# DVforArduino.net
KiCad netlist of a schematic drawn in EAGLE
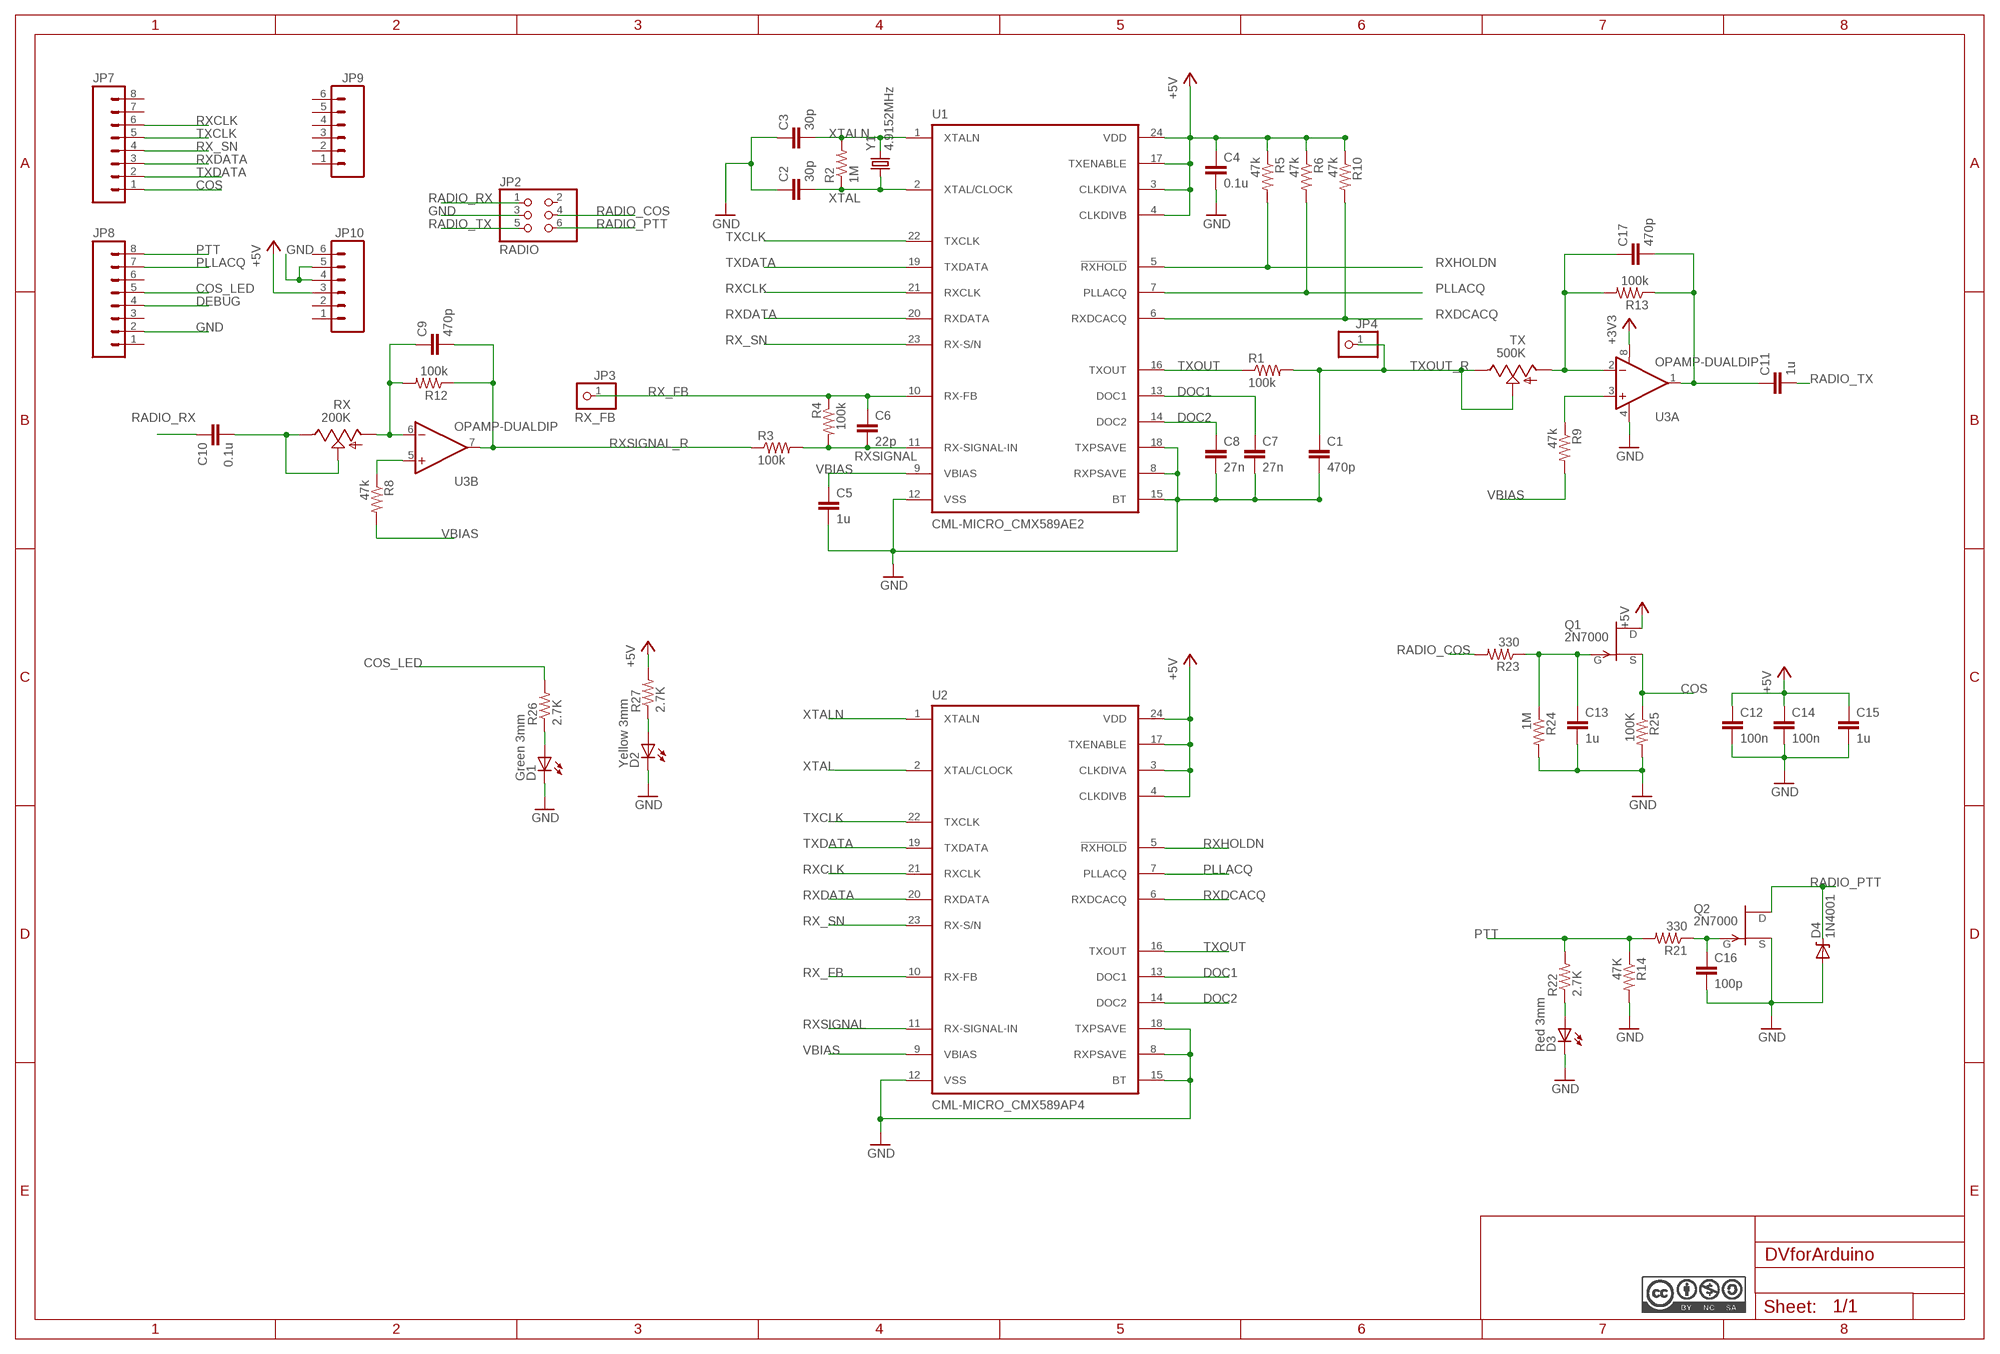
[diagram p0: schematic, sheet 1]

(export (version "E")
  (design (tool "Eeschema 10.0.6"))
  (components
    (comp (ref "C1")
      (value "470p")
      (footprint "eagle-import:C2.5-3")
      (libsource (lib "eagle-import") (part "C2,5-3"))
    )
    (comp (ref "C2")
      (value "30p")
      (footprint "eagle-import:C2.5-3")
      (libsource (lib "eagle-import") (part "C2,5-3"))
    )
    (comp (ref "C3")
      (value "30p")
      (footprint "eagle-import:C2.5-3")
      (libsource (lib "eagle-import") (part "C2,5-3"))
    )
    (comp (ref "C4")
      (value "0.1u")
      (footprint "eagle-import:C2.5-3")
      (libsource (lib "eagle-import") (part "C2,5-3"))
    )
    (comp (ref "C5")
      (value "1u")
      (footprint "eagle-import:C2.5-3")
      (libsource (lib "eagle-import") (part "C2,5-3"))
    )
    (comp (ref "C6")
      (value "22p")
      (footprint "eagle-import:C2.5-3")
      (libsource (lib "eagle-import") (part "C2,5-3"))
    )
    (comp (ref "C7")
      (value "27n")
      (footprint "eagle-import:C2.5-3")
      (libsource (lib "eagle-import") (part "C2,5-3"))
    )
    (comp (ref "C8")
      (value "27n")
      (footprint "eagle-import:C2.5-3")
      (libsource (lib "eagle-import") (part "C2,5-3"))
    )
    (comp (ref "C9")
      (value "470p")
      (footprint "eagle-import:C2.5-3")
      (libsource (lib "eagle-import") (part "C2,5-3"))
    )
    (comp (ref "C10")
      (value "0.1u")
      (footprint "eagle-import:C2.5-3")
      (libsource (lib "eagle-import") (part "C2,5-3"))
    )
    (comp (ref "C11")
      (value "1u")
      (footprint "eagle-import:C2.5-3")
      (libsource (lib "eagle-import") (part "C2,5-3"))
    )
    (comp (ref "C12")
      (value "100n")
      (footprint "eagle-import:C2.5-3")
      (libsource (lib "eagle-import") (part "C2,5-3"))
    )
    (comp (ref "C13")
      (value "1u")
      (footprint "eagle-import:C2.5-3")
      (libsource (lib "eagle-import") (part "C2,5-3"))
    )
    (comp (ref "C14")
      (value "100n")
      (footprint "eagle-import:C2.5-3")
      (libsource (lib "eagle-import") (part "C2,5-3"))
    )
    (comp (ref "C15")
      (value "1u")
      (footprint "eagle-import:C2.5-3")
      (libsource (lib "eagle-import") (part "C2,5-3"))
    )
    (comp (ref "C16")
      (value "100p")
      (footprint "eagle-import:C2.5-3")
      (libsource (lib "eagle-import") (part "C2,5-3"))
    )
    (comp (ref "C17")
      (value "470p")
      (footprint "eagle-import:C2.5-3")
      (libsource (lib "eagle-import") (part "C2,5-3"))
    )
    (comp (ref "D1")
      (value "Green 3mm")
      (footprint "eagle-import:LED3MM")
      (libsource (lib "eagle-import") (part "LED3MM"))
    )
    (comp (ref "D2")
      (value "Yellow 3mm")
      (footprint "eagle-import:LED3MM")
      (libsource (lib "eagle-import") (part "LED3MM"))
    )
    (comp (ref "D3")
      (value "Red 3mm")
      (footprint "eagle-import:LED3MM")
      (libsource (lib "eagle-import") (part "LED3MM"))
    )
    (comp (ref "D4")
      (value "1N4001")
      (footprint "eagle-import:DIODE-ZENER")
      (libsource (lib "eagle-import") (part "DIODE-ZENERPTH"))
    )
    (comp (ref "JP2")
      (value "RADIO")
      (footprint "eagle-import:2X03_ROUND_70MIL")
      (libsource (lib "eagle-import") (part "HEADER-2X3"))
    )
    (comp (ref "JP3")
      (value "RX_FB")
      (footprint "eagle-import:1X01_ROUND")
      (libsource (lib "eagle-import") (part "HEADER-1X1ROUND"))
    )
    (comp (ref "JP4")
      (value "HEADER-1X1ROUND")
      (footprint "eagle-import:1X01_ROUND")
      (libsource (lib "eagle-import") (part "HEADER-1X1ROUND"))
    )
    (comp (ref "JP7")
      (value "M081X08")
      (footprint "eagle-import:1X08")
      (libsource (lib "eagle-import") (part "M081X08"))
    )
    (comp (ref "JP8")
      (value "M081X08")
      (footprint "eagle-import:1X08")
      (libsource (lib "eagle-import") (part "M081X08"))
    )
    (comp (ref "JP9")
      (value "M06SIP")
      (footprint "eagle-import:1X06")
      (libsource (lib "eagle-import") (part "M06SIP"))
    )
    (comp (ref "JP10")
      (value "M06SIP")
      (footprint "eagle-import:1X06")
      (libsource (lib "eagle-import") (part "M06SIP"))
    )
    (comp (ref "Q1")
      (value "2N7000")
      (footprint "eagle-import:TO92")
      (libsource (lib "eagle-import") (part "2N3819"))
    )
    (comp (ref "Q2")
      (value "2N7000")
      (footprint "eagle-import:TO92")
      (libsource (lib "eagle-import") (part "2N3819"))
    )
    (comp (ref "R1")
      (value "100k")
      (footprint "eagle-import:0204V")
      (libsource (lib "eagle-import") (part "R-US_0204/2V"))
    )
    (comp (ref "R2")
      (value "1M")
      (footprint "eagle-import:0204V")
      (libsource (lib "eagle-import") (part "R-US_0204/2V"))
    )
    (comp (ref "R3")
      (value "100k")
      (footprint "eagle-import:0204V")
      (libsource (lib "eagle-import") (part "R-US_0204/2V"))
    )
    (comp (ref "R4")
      (value "100k")
      (footprint "eagle-import:0204V")
      (libsource (lib "eagle-import") (part "R-US_0204/2V"))
    )
    (comp (ref "R5")
      (value "47k")
      (footprint "eagle-import:0204V")
      (libsource (lib "eagle-import") (part "R-US_0204/2V"))
    )
    (comp (ref "R6")
      (value "47k")
      (footprint "eagle-import:0204V")
      (libsource (lib "eagle-import") (part "R-US_0204/2V"))
    )
    (comp (ref "R8")
      (value "47k")
      (footprint "eagle-import:0204V")
      (libsource (lib "eagle-import") (part "R-US_0204/2V"))
    )
    (comp (ref "R9")
      (value "47k")
      (footprint "eagle-import:0204V")
      (libsource (lib "eagle-import") (part "R-US_0204/2V"))
    )
    (comp (ref "R10")
      (value "47k")
      (footprint "eagle-import:0204V")
      (libsource (lib "eagle-import") (part "R-US_0204/2V"))
    )
    (comp (ref "R12")
      (value "100k")
      (footprint "eagle-import:0204V")
      (libsource (lib "eagle-import") (part "R-US_0204/2V"))
    )
    (comp (ref "R13")
      (value "100k")
      (footprint "eagle-import:0204V")
      (libsource (lib "eagle-import") (part "R-US_0204/2V"))
    )
    (comp (ref "R14")
      (value "47K")
      (footprint "eagle-import:0204V")
      (libsource (lib "eagle-import") (part "R-US_0204/2V"))
    )
    (comp (ref "R21")
      (value "330")
      (footprint "eagle-import:0204V")
      (libsource (lib "eagle-import") (part "R-US_0204/2V"))
    )
    (comp (ref "R22")
      (value "2.7K")
      (footprint "eagle-import:0204V")
      (libsource (lib "eagle-import") (part "R-US_0204/2V"))
    )
    (comp (ref "R23")
      (value "330")
      (footprint "eagle-import:0204V")
      (libsource (lib "eagle-import") (part "R-US_0204/2V"))
    )
    (comp (ref "R24")
      (value "1M")
      (footprint "eagle-import:0204V")
      (libsource (lib "eagle-import") (part "R-US_0204/2V"))
    )
    (comp (ref "R25")
      (value "100K")
      (footprint "eagle-import:0204V")
      (libsource (lib "eagle-import") (part "R-US_0204/2V"))
    )
    (comp (ref "R26")
      (value "2.7K")
      (footprint "eagle-import:0204V")
      (libsource (lib "eagle-import") (part "R-US_0204/2V"))
    )
    (comp (ref "R27")
      (value "2.7K")
      (footprint "eagle-import:0204V")
      (libsource (lib "eagle-import") (part "R-US_0204/2V"))
    )
    (comp (ref "RX")
      (value "200K")
      (footprint "eagle-import:B25P")
      (libsource (lib "eagle-import") (part "TRIM_US-B25P"))
    )
    (comp (ref "TX")
      (value "500K")
      (footprint "eagle-import:B25P")
      (libsource (lib "eagle-import") (part "TRIM_US-B25P"))
    )
    (comp (ref "U1")
      (value "CML-MICRO_CMX589AE2")
      (footprint "eagle-import:AIS_MK2_CML-MICRO_TSSOP24")
      (libsource (lib "eagle-import") (part "AIS_MK2_CML-MICRO_CMX589AE2"))
    )
    (comp (ref "U2")
      (value "CML-MICRO_CMX589AP4")
      (footprint "eagle-import:AIS_MK2_CML-MICRO_DIL24-6")
      (libsource (lib "eagle-import") (part "AIS_MK2_CML-MICRO_CMX589AP4"))
    )
    (comp (ref "U3")
      (value "OPAMP-DUALDIP")
      (footprint "eagle-import:DIP08")
      (libsource (lib "eagle-import") (part "OPAMP-DUALDIP"))
    )
    (comp (ref "Y1")
      (value "4.9152MHz")
      (footprint "eagle-import:HC49US")
      (libsource (lib "eagle-import") (part "CRYSTALHC49US"))
    )
  )
  (nets
    (net (code "1") (name "+3V3") (class "Default")
      (node (ref "C12") (pin "1") (pinfunction "1_1") (pintype "passive"))
      (node (ref "C14") (pin "1") (pinfunction "1_1") (pintype "passive"))
      (node (ref "C15") (pin "1") (pinfunction "1_1") (pintype "passive"))
      (node (ref "C4") (pin "1") (pinfunction "1_1") (pintype "passive"))
      (node (ref "JP10") (pin "3") (pinfunction "3_3") (pintype "passive"))
      (node (ref "Q1") (pin "1") (pinfunction "D_1") (pintype "passive"))
      (node (ref "R10") (pin "1") (pinfunction "1_1") (pintype "passive"))
      (node (ref "R27") (pin "2") (pinfunction "2_2") (pintype "passive"))
      (node (ref "R5") (pin "1") (pinfunction "1_1") (pintype "passive"))
      (node (ref "R6") (pin "1") (pinfunction "1_1") (pintype "passive"))
      (node (ref "U1") (pin "17") (pinfunction "TXENABLE_17") (pintype "input"))
      (node (ref "U1") (pin "24") (pinfunction "VDD_24") (pintype "power_in"))
      (node (ref "U1") (pin "3") (pinfunction "CLKDIVA_3") (pintype "input"))
      (node (ref "U1") (pin "4") (pinfunction "CLKDIVB_4") (pintype "input"))
      (node (ref "U2") (pin "17") (pinfunction "TXENABLE_17") (pintype "input"))
      (node (ref "U2") (pin "24") (pinfunction "VDD_24") (pintype "power_in"))
      (node (ref "U2") (pin "3") (pinfunction "CLKDIVA_3") (pintype "input"))
      (node (ref "U2") (pin "4") (pinfunction "CLKDIVB_4") (pintype "input"))
      (node (ref "U3") (pin "8") (pinfunction "V+_8") (pintype "power_in"))
    )
    (net (code "2") (name "/COS") (class "Default")
      (node (ref "JP7") (pin "1") (pinfunction "1_1") (pintype "passive"))
      (node (ref "Q1") (pin "3") (pinfunction "S_3") (pintype "passive"))
      (node (ref "R25") (pin "1") (pinfunction "1_1") (pintype "passive"))
    )
    (net (code "3") (name "/COS_LED") (class "Default")
      (node (ref "JP8") (pin "5") (pinfunction "5_5") (pintype "passive"))
      (node (ref "R26") (pin "2") (pinfunction "2_2") (pintype "passive"))
    )
    (net (code "4") (name "/DEBUG") (class "Default")
      (node (ref "JP8") (pin "4") (pinfunction "4_4") (pintype "passive"))
    )
    (net (code "5") (name "/DOC1") (class "Default")
      (node (ref "C7") (pin "1") (pinfunction "1_1") (pintype "passive"))
      (node (ref "U1") (pin "13") (pinfunction "DOC1_13") (pintype "passive"))
      (node (ref "U2") (pin "13") (pinfunction "DOC1_13") (pintype "passive"))
    )
    (net (code "6") (name "/DOC2") (class "Default")
      (node (ref "C8") (pin "1") (pinfunction "1_1") (pintype "passive"))
      (node (ref "U1") (pin "14") (pinfunction "DOC2_14") (pintype "passive"))
      (node (ref "U2") (pin "14") (pinfunction "DOC2_14") (pintype "passive"))
    )
    (net (code "7") (name "/PLLACQ") (class "Default")
      (node (ref "JP8") (pin "7") (pinfunction "7_7") (pintype "passive"))
      (node (ref "R6") (pin "2") (pinfunction "2_2") (pintype "passive"))
      (node (ref "U1") (pin "7") (pinfunction "PLLACQ_7") (pintype "input"))
      (node (ref "U2") (pin "7") (pinfunction "PLLACQ_7") (pintype "input"))
    )
    (net (code "8") (name "/PTT") (class "Default")
      (node (ref "JP8") (pin "8") (pinfunction "8_8") (pintype "passive"))
      (node (ref "R14") (pin "1") (pinfunction "1_1") (pintype "passive"))
      (node (ref "R21") (pin "2") (pinfunction "2_2") (pintype "passive"))
      (node (ref "R22") (pin "2") (pinfunction "2_2") (pintype "passive"))
    )
    (net (code "9") (name "/RADIO_COS") (class "Default")
      (node (ref "JP2") (pin "4") (pinfunction "4_4") (pintype "passive"))
      (node (ref "R23") (pin "2") (pinfunction "2_2") (pintype "passive"))
    )
    (net (code "10") (name "/RADIO_PTT") (class "Default")
      (node (ref "D4") (pin "P$1") (pinfunction "C_P$1") (pintype "passive"))
      (node (ref "JP2") (pin "6") (pinfunction "6_6") (pintype "passive"))
      (node (ref "Q2") (pin "1") (pinfunction "D_1") (pintype "passive"))
    )
    (net (code "11") (name "/RADIO_RX") (class "Default")
      (node (ref "C10") (pin "1") (pinfunction "1_1") (pintype "passive"))
      (node (ref "JP2") (pin "1") (pinfunction "1_1") (pintype "passive"))
    )
    (net (code "12") (name "/RADIO_TX") (class "Default")
      (node (ref "C11") (pin "2") (pinfunction "2_2") (pintype "passive"))
      (node (ref "JP2") (pin "5") (pinfunction "5_5") (pintype "passive"))
    )
    (net (code "13") (name "/RXCLK") (class "Default")
      (node (ref "JP7") (pin "6") (pinfunction "6_6") (pintype "passive"))
      (node (ref "U1") (pin "21") (pinfunction "RXCLK_21") (pintype "output"))
      (node (ref "U2") (pin "21") (pinfunction "RXCLK_21") (pintype "output"))
    )
    (net (code "14") (name "/RXDATA") (class "Default")
      (node (ref "JP7") (pin "3") (pinfunction "3_3") (pintype "passive"))
      (node (ref "U1") (pin "20") (pinfunction "RXDATA_20") (pintype "output"))
      (node (ref "U2") (pin "20") (pinfunction "RXDATA_20") (pintype "output"))
    )
    (net (code "15") (name "/RXDCACQ") (class "Default")
      (node (ref "R10") (pin "2") (pinfunction "2_2") (pintype "passive"))
      (node (ref "U1") (pin "6") (pinfunction "RXDCACQ_6") (pintype "input"))
      (node (ref "U2") (pin "6") (pinfunction "RXDCACQ_6") (pintype "input"))
    )
    (net (code "16") (name "/RXHOLDN") (class "Default")
      (node (ref "R5") (pin "2") (pinfunction "2_2") (pintype "passive"))
      (node (ref "U1") (pin "5") (pinfunction "~{RXHOLD}_5") (pintype "input"))
      (node (ref "U2") (pin "5") (pinfunction "~{RXHOLD}_5") (pintype "input"))
    )
    (net (code "17") (name "/RXSIGNAL") (class "Default")
      (node (ref "C6") (pin "2") (pinfunction "2_2") (pintype "passive"))
      (node (ref "R3") (pin "2") (pinfunction "2_2") (pintype "passive"))
      (node (ref "R4") (pin "2") (pinfunction "2_2") (pintype "passive"))
      (node (ref "U1") (pin "11") (pinfunction "RX-SIGNAL-IN_11") (pintype "input"))
      (node (ref "U2") (pin "11") (pinfunction "RX-SIGNAL-IN_11") (pintype "input"))
    )
    (net (code "18") (name "/RXSIGNAL_R") (class "Default")
      (node (ref "C9") (pin "2") (pinfunction "2_2") (pintype "passive"))
      (node (ref "R12") (pin "1") (pinfunction "1_1") (pintype "passive"))
      (node (ref "R3") (pin "1") (pinfunction "1_1") (pintype "passive"))
      (node (ref "U3") (pin "7") (pinfunction "OUT_7") (pintype "output"))
    )
    (net (code "19") (name "/RX_FB") (class "Default")
      (node (ref "C6") (pin "1") (pinfunction "1_1") (pintype "passive"))
      (node (ref "JP3") (pin "1") (pinfunction "1_1") (pintype "passive"))
      (node (ref "R4") (pin "1") (pinfunction "1_1") (pintype "passive"))
      (node (ref "U1") (pin "10") (pinfunction "RX-FB_10") (pintype "input"))
      (node (ref "U2") (pin "10") (pinfunction "RX-FB_10") (pintype "input"))
    )
    (net (code "20") (name "/RX_SN") (class "Default")
      (node (ref "JP7") (pin "4") (pinfunction "4_4") (pintype "passive"))
      (node (ref "U1") (pin "23") (pinfunction "RX-S/N_23") (pintype "output"))
      (node (ref "U2") (pin "23") (pinfunction "RX-S/N_23") (pintype "output"))
    )
    (net (code "21") (name "/TXCLK") (class "Default")
      (node (ref "JP7") (pin "5") (pinfunction "5_5") (pintype "passive"))
      (node (ref "U1") (pin "22") (pinfunction "TXCLK_22") (pintype "output"))
      (node (ref "U2") (pin "22") (pinfunction "TXCLK_22") (pintype "output"))
    )
    (net (code "22") (name "/TXDATA") (class "Default")
      (node (ref "JP7") (pin "2") (pinfunction "2_2") (pintype "passive"))
      (node (ref "U1") (pin "19") (pinfunction "TXDATA_19") (pintype "input"))
      (node (ref "U2") (pin "19") (pinfunction "TXDATA_19") (pintype "input"))
    )
    (net (code "23") (name "/TXOUT") (class "Default")
      (node (ref "R1") (pin "1") (pinfunction "1_1") (pintype "passive"))
      (node (ref "U1") (pin "16") (pinfunction "TXOUT_16") (pintype "output"))
      (node (ref "U2") (pin "16") (pinfunction "TXOUT_16") (pintype "output"))
    )
    (net (code "24") (name "/TXOUT_R") (class "Default")
      (node (ref "C1") (pin "1") (pinfunction "1_1") (pintype "passive"))
      (node (ref "JP4") (pin "1") (pinfunction "1_1") (pintype "passive"))
      (node (ref "R1") (pin "2") (pinfunction "2_2") (pintype "passive"))
      (node (ref "TX") (pin "E") (pinfunction "E_E") (pintype "passive"))
      (node (ref "TX") (pin "S") (pinfunction "S_S") (pintype "passive"))
    )
    (net (code "25") (name "/VBIAS") (class "Default")
      (node (ref "C5") (pin "1") (pinfunction "1_1") (pintype "passive"))
      (node (ref "R8") (pin "2") (pinfunction "2_2") (pintype "passive"))
      (node (ref "R9") (pin "2") (pinfunction "2_2") (pintype "passive"))
      (node (ref "U1") (pin "9") (pinfunction "VBIAS_9") (pintype "input"))
      (node (ref "U2") (pin "9") (pinfunction "VBIAS_9") (pintype "input"))
    )
    (net (code "26") (name "/XTAL") (class "Default")
      (node (ref "C2") (pin "2") (pinfunction "2_2") (pintype "passive"))
      (node (ref "R2") (pin "1") (pinfunction "1_1") (pintype "passive"))
      (node (ref "U1") (pin "2") (pinfunction "XTAL/CLOCK_2") (pintype "input"))
      (node (ref "U2") (pin "2") (pinfunction "XTAL/CLOCK_2") (pintype "input"))
      (node (ref "Y1") (pin "1") (pinfunction "1_1") (pintype "passive"))
    )
    (net (code "27") (name "/XTALN") (class "Default")
      (node (ref "C3") (pin "2") (pinfunction "2_2") (pintype "passive"))
      (node (ref "R2") (pin "2") (pinfunction "2_2") (pintype "passive"))
      (node (ref "U1") (pin "1") (pinfunction "XTALN_1") (pintype "output"))
      (node (ref "U2") (pin "1") (pinfunction "XTALN_1") (pintype "output"))
      (node (ref "Y1") (pin "2") (pinfunction "2_2") (pintype "passive"))
    )
    (net (code "28") (name "GND") (class "Default")
      (node (ref "C1") (pin "2") (pinfunction "2_2") (pintype "passive"))
      (node (ref "C12") (pin "2") (pinfunction "2_2") (pintype "passive"))
      (node (ref "C13") (pin "2") (pinfunction "2_2") (pintype "passive"))
      (node (ref "C14") (pin "2") (pinfunction "2_2") (pintype "passive"))
      (node (ref "C15") (pin "2") (pinfunction "2_2") (pintype "passive"))
      (node (ref "C16") (pin "2") (pinfunction "2_2") (pintype "passive"))
      (node (ref "C2") (pin "1") (pinfunction "1_1") (pintype "passive"))
      (node (ref "C3") (pin "1") (pinfunction "1_1") (pintype "passive"))
      (node (ref "C4") (pin "2") (pinfunction "2_2") (pintype "passive"))
      (node (ref "C5") (pin "2") (pinfunction "2_2") (pintype "passive"))
      (node (ref "C7") (pin "2") (pinfunction "2_2") (pintype "passive"))
      (node (ref "C8") (pin "2") (pinfunction "2_2") (pintype "passive"))
      (node (ref "D1") (pin "K") (pinfunction "C_K") (pintype "passive"))
      (node (ref "D2") (pin "K") (pinfunction "C_K") (pintype "passive"))
      (node (ref "D3") (pin "K") (pinfunction "C_K") (pintype "passive"))
      (node (ref "D4") (pin "P$2") (pinfunction "A_P$2") (pintype "passive"))
      (node (ref "JP10") (pin "4") (pinfunction "4_4") (pintype "passive"))
      (node (ref "JP10") (pin "5") (pinfunction "5_5") (pintype "passive"))
      (node (ref "JP2") (pin "3") (pinfunction "3_3") (pintype "passive"))
      (node (ref "JP8") (pin "2") (pinfunction "2_2") (pintype "passive"))
      (node (ref "Q2") (pin "3") (pinfunction "S_3") (pintype "passive"))
      (node (ref "R14") (pin "2") (pinfunction "2_2") (pintype "passive"))
      (node (ref "R24") (pin "2") (pinfunction "2_2") (pintype "passive"))
      (node (ref "R25") (pin "2") (pinfunction "2_2") (pintype "passive"))
      (node (ref "U1") (pin "12") (pinfunction "VSS_12") (pintype "power_in"))
      (node (ref "U1") (pin "15") (pinfunction "BT_15") (pintype "input"))
      (node (ref "U1") (pin "18") (pinfunction "TXPSAVE_18") (pintype "input"))
      (node (ref "U1") (pin "8") (pinfunction "RXPSAVE_8") (pintype "input"))
      (node (ref "U2") (pin "12") (pinfunction "VSS_12") (pintype "power_in"))
      (node (ref "U2") (pin "15") (pinfunction "BT_15") (pintype "input"))
      (node (ref "U2") (pin "18") (pinfunction "TXPSAVE_18") (pintype "input"))
      (node (ref "U2") (pin "8") (pinfunction "RXPSAVE_8") (pintype "input"))
      (node (ref "U3") (pin "4") (pinfunction "V-_4") (pintype "power_in"))
    )
    (net (code "29") (name "Net-(C10-Pad2)") (class "Default")
      (node (ref "C10") (pin "2") (pinfunction "2_2") (pintype "passive"))
      (node (ref "RX") (pin "E") (pinfunction "E_E") (pintype "passive"))
      (node (ref "RX") (pin "S") (pinfunction "S_S") (pintype "passive"))
    )
    (net (code "30") (name "Net-(D1-PadA)") (class "Default")
      (node (ref "D1") (pin "A") (pinfunction "A_A") (pintype "passive"))
      (node (ref "R26") (pin "1") (pinfunction "1_1") (pintype "passive"))
    )
    (net (code "31") (name "Net-(D2-PadA)") (class "Default")
      (node (ref "D2") (pin "A") (pinfunction "A_A") (pintype "passive"))
      (node (ref "R27") (pin "1") (pinfunction "1_1") (pintype "passive"))
    )
    (net (code "32") (name "Net-(D3-PadA)") (class "Default")
      (node (ref "D3") (pin "A") (pinfunction "A_A") (pintype "passive"))
      (node (ref "R22") (pin "1") (pinfunction "1_1") (pintype "passive"))
    )
    (net (code "33") (name "Net-(Q1-G)") (class "Default")
      (node (ref "C13") (pin "1") (pinfunction "1_1") (pintype "passive"))
      (node (ref "Q1") (pin "2") (pinfunction "G_2") (pintype "passive"))
      (node (ref "R23") (pin "1") (pinfunction "1_1") (pintype "passive"))
      (node (ref "R24") (pin "1") (pinfunction "1_1") (pintype "passive"))
    )
    (net (code "34") (name "Net-(Q2-G)") (class "Default")
      (node (ref "C16") (pin "1") (pinfunction "1_1") (pintype "passive"))
      (node (ref "Q2") (pin "2") (pinfunction "G_2") (pintype "passive"))
      (node (ref "R21") (pin "1") (pinfunction "1_1") (pintype "passive"))
    )
    (net (code "35") (name "Net-(U3A-+IN)") (class "Default")
      (node (ref "R9") (pin "1") (pinfunction "1_1") (pintype "passive"))
      (node (ref "U3") (pin "3") (pinfunction "+IN_3") (pintype "input"))
    )
    (net (code "36") (name "Net-(U3A--IN)") (class "Default")
      (node (ref "C17") (pin "1") (pinfunction "1_1") (pintype "passive"))
      (node (ref "R13") (pin "2") (pinfunction "2_2") (pintype "passive"))
      (node (ref "TX") (pin "A") (pinfunction "A_A") (pintype "passive"))
      (node (ref "U3") (pin "2") (pinfunction "-IN_2") (pintype "input"))
    )
    (net (code "37") (name "Net-(U3A-OUT)") (class "Default")
      (node (ref "C11") (pin "1") (pinfunction "1_1") (pintype "passive"))
      (node (ref "C17") (pin "2") (pinfunction "2_2") (pintype "passive"))
      (node (ref "R13") (pin "1") (pinfunction "1_1") (pintype "passive"))
      (node (ref "U3") (pin "1") (pinfunction "OUT_1") (pintype "output"))
    )
    (net (code "38") (name "Net-(U3B-+IN)") (class "Default")
      (node (ref "R8") (pin "1") (pinfunction "1_1") (pintype "passive"))
      (node (ref "U3") (pin "5") (pinfunction "+IN_5") (pintype "input"))
    )
    (net (code "39") (name "Net-(U3B--IN)") (class "Default")
      (node (ref "C9") (pin "1") (pinfunction "1_1") (pintype "passive"))
      (node (ref "R12") (pin "2") (pinfunction "2_2") (pintype "passive"))
      (node (ref "RX") (pin "A") (pinfunction "A_A") (pintype "passive"))
      (node (ref "U3") (pin "6") (pinfunction "-IN_6") (pintype "input"))
    )
    (net (code "40") (name "unconnected-(JP2-Pad2)") (class "Default")
      (node (ref "JP2") (pin "2") (pinfunction "2_2") (pintype "passive"))
    )
    (net (code "41") (name "unconnected-(JP7-Pad7)") (class "Default")
      (node (ref "JP7") (pin "7") (pinfunction "7_7") (pintype "passive"))
    )
    (net (code "42") (name "unconnected-(JP7-Pad8)") (class "Default")
      (node (ref "JP7") (pin "8") (pinfunction "8_8") (pintype "passive"))
    )
    (net (code "43") (name "unconnected-(JP8-Pad1)") (class "Default")
      (node (ref "JP8") (pin "1") (pinfunction "1_1") (pintype "passive"))
    )
    (net (code "44") (name "unconnected-(JP8-Pad3)") (class "Default")
      (node (ref "JP8") (pin "3") (pinfunction "3_3") (pintype "passive"))
    )
    (net (code "45") (name "unconnected-(JP8-Pad6)") (class "Default")
      (node (ref "JP8") (pin "6") (pinfunction "6_6") (pintype "passive"))
    )
    (net (code "46") (name "unconnected-(JP9-Pad1)") (class "Default")
      (node (ref "JP9") (pin "1") (pinfunction "1_1") (pintype "passive"))
    )
    (net (code "47") (name "unconnected-(JP9-Pad2)") (class "Default")
      (node (ref "JP9") (pin "2") (pinfunction "2_2") (pintype "passive"))
    )
    (net (code "48") (name "unconnected-(JP9-Pad3)") (class "Default")
      (node (ref "JP9") (pin "3") (pinfunction "3_3") (pintype "passive"))
    )
    (net (code "49") (name "unconnected-(JP9-Pad4)") (class "Default")
      (node (ref "JP9") (pin "4") (pinfunction "4_4") (pintype "passive"))
    )
    (net (code "50") (name "unconnected-(JP9-Pad5)") (class "Default")
      (node (ref "JP9") (pin "5") (pinfunction "5_5") (pintype "passive"))
    )
    (net (code "51") (name "unconnected-(JP9-Pad6)") (class "Default")
      (node (ref "JP9") (pin "6") (pinfunction "6_6") (pintype "passive"))
    )
    (net (code "52") (name "unconnected-(JP10-Pad1)") (class "Default")
      (node (ref "JP10") (pin "1") (pinfunction "1_1") (pintype "passive"))
    )
    (net (code "53") (name "unconnected-(JP10-Pad2)") (class "Default")
      (node (ref "JP10") (pin "2") (pinfunction "2_2") (pintype "passive"))
    )
    (net (code "54") (name "unconnected-(JP10-Pad6)") (class "Default")
      (node (ref "JP10") (pin "6") (pinfunction "6_6") (pintype "passive"))
    )
  )
)
